# Ble_multimeter.net
KiCad netlist of a schematic drawn in EAGLE
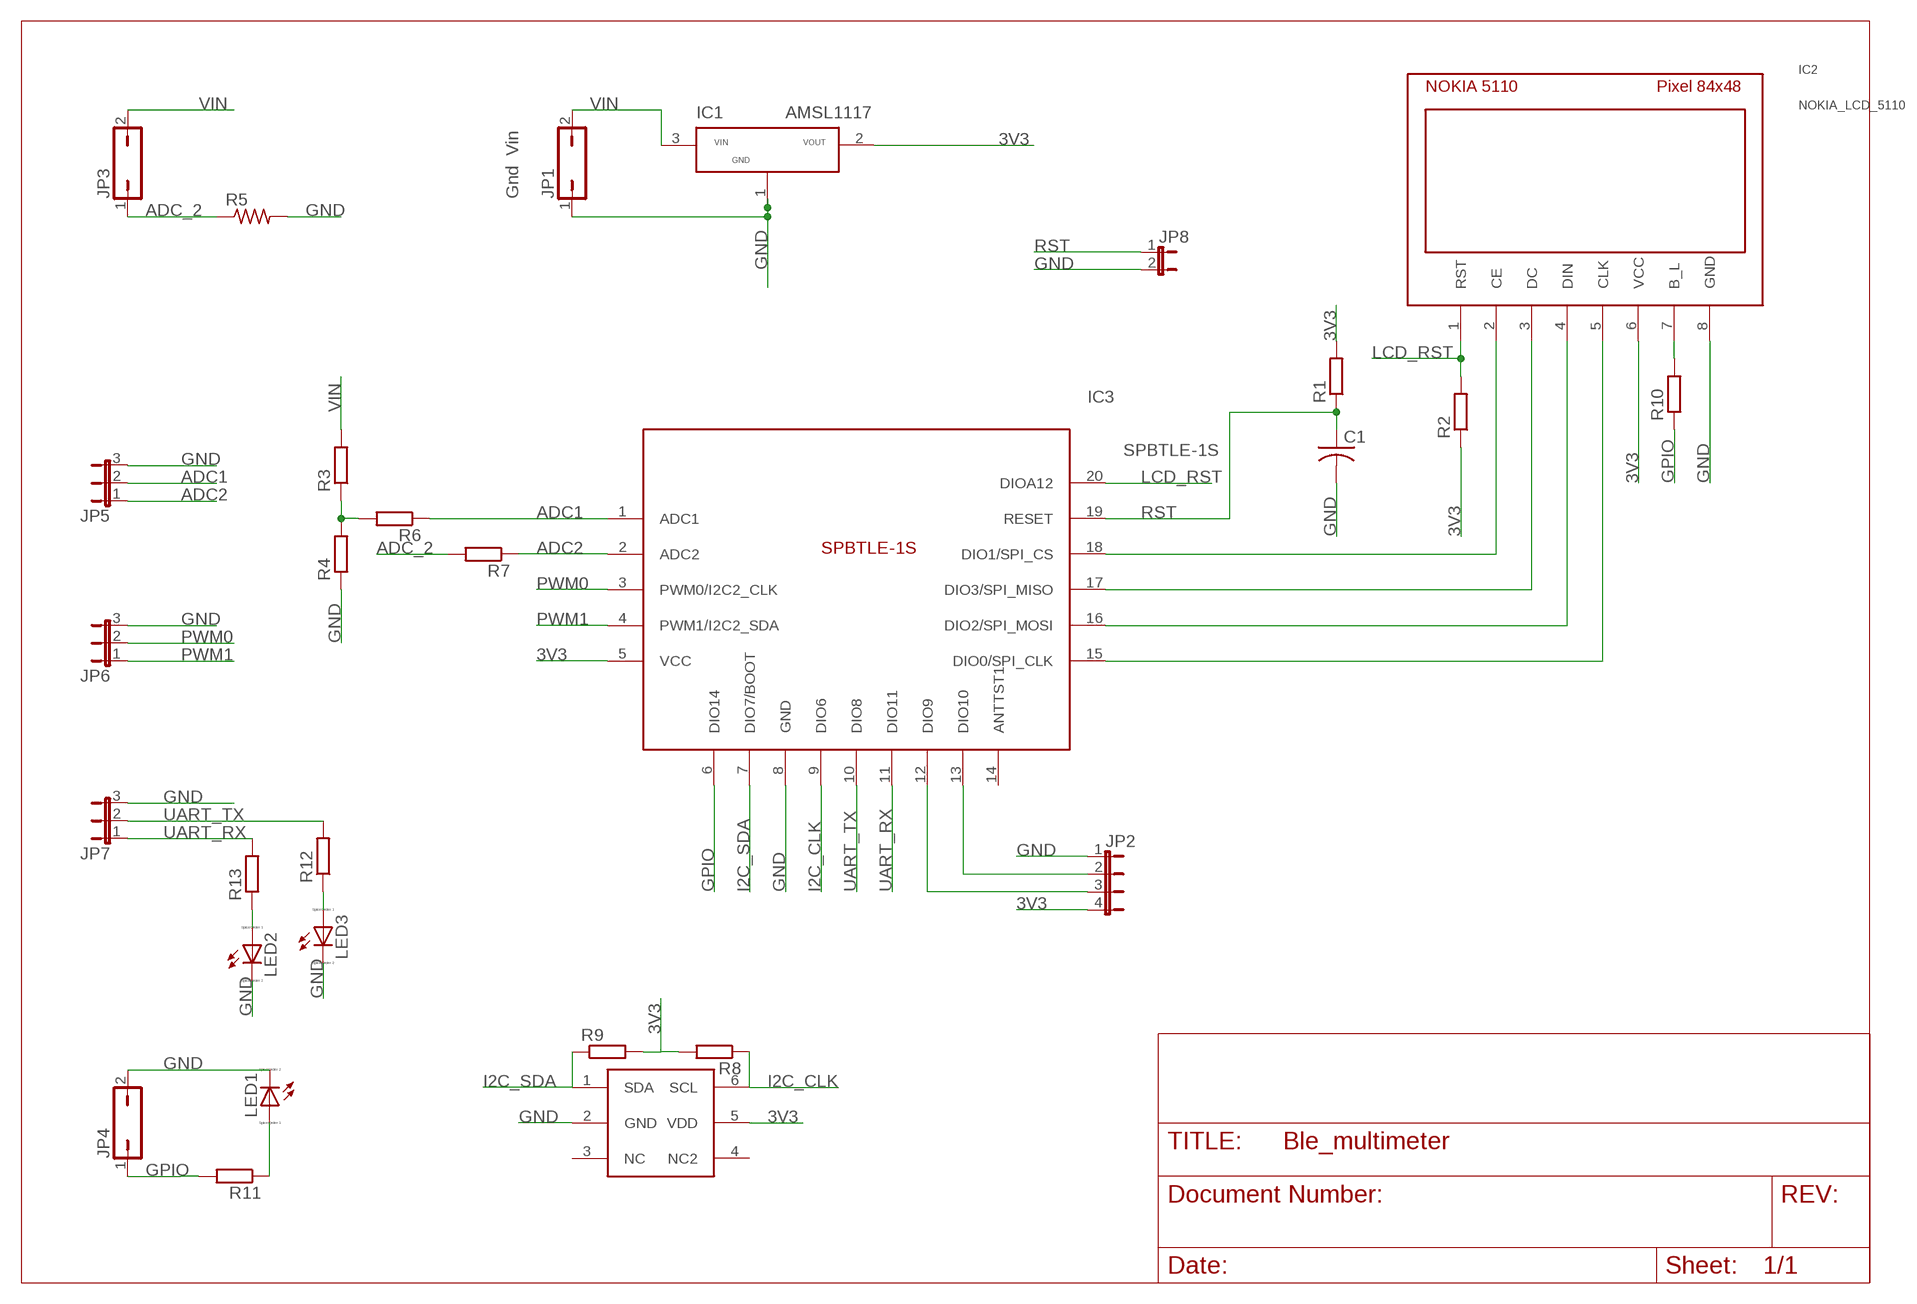
[diagram p0: schematic, sheet 1]

(export (version "E")
  (design (tool "Eeschema 10.0.6"))
  (components
    (comp (ref "C1")
      (value "C-USC0805")
      (footprint "eagle-import:C0805")
      (libsource (lib "eagle-import") (part "C-USC0805"))
    )
    (comp (ref "IC1")
      (value "AMSL1117")
      (footprint "eagle-import:SOT223")
      (libsource (lib "eagle-import") (part "AMSL1117"))
    )
    (comp (ref "IC2")
      (value "NOKIA_LCD_5110")
      (footprint "eagle-import:NOKIA_LCD_5110_8PIN")
      (libsource (lib "eagle-import") (part "NOKIA_LCD_5110"))
    )
    (comp (ref "IC3")
      (value "SPBTLE-1S")
      (footprint "eagle-import:SPBTLE-1S_SMD20")
      (libsource (lib "eagle-import") (part "SPBTLE-1S"))
    )
    (comp (ref "IC4")
      (value "HDC1080")
      (footprint "eagle-import:6_PIN_PWSON")
      (libsource (lib "eagle-import") (part "HDC1080"))
    )
    (comp (ref "JP1")
      (value "JP1Q")
      (footprint "eagle-import:JP1")
      (libsource (lib "eagle-import") (part "JP1Q"))
    )
    (comp (ref "JP2")
      (value "JP4E")
      (footprint "eagle-import:JP4")
      (libsource (lib "eagle-import") (part "JP4E"))
    )
    (comp (ref "JP3")
      (value "JP1Q")
      (footprint "eagle-import:JP1")
      (libsource (lib "eagle-import") (part "JP1Q"))
    )
    (comp (ref "JP4")
      (value "JP1Q")
      (footprint "eagle-import:JP1")
      (libsource (lib "eagle-import") (part "JP1Q"))
    )
    (comp (ref "JP5")
      (value "JP2E")
      (footprint "eagle-import:JP2")
      (libsource (lib "eagle-import") (part "JP2E"))
    )
    (comp (ref "JP6")
      (value "JP2E")
      (footprint "eagle-import:JP2")
      (libsource (lib "eagle-import") (part "JP2E"))
    )
    (comp (ref "JP7")
      (value "JP2E")
      (footprint "eagle-import:JP2")
      (libsource (lib "eagle-import") (part "JP2E"))
    )
    (comp (ref "JP8")
      (value "JP1E")
      (footprint "eagle-import:JP1")
      (libsource (lib "eagle-import") (part "JP1E"))
    )
    (comp (ref "LED1")
      (value "LED_E")
      (footprint "eagle-import:LED_1206")
      (libsource (lib "eagle-import") (part "LED_E"))
    )
    (comp (ref "LED2")
      (value "LED_E")
      (footprint "eagle-import:LED_1206")
      (libsource (lib "eagle-import") (part "LED_E"))
    )
    (comp (ref "LED3")
      (value "LED_E")
      (footprint "eagle-import:LED_1206")
      (libsource (lib "eagle-import") (part "LED_E"))
    )
    (comp (ref "R1")
      (value "R-EU_M1206")
      (footprint "eagle-import:M1206")
      (libsource (lib "eagle-import") (part "R-EU_M1206"))
    )
    (comp (ref "R2")
      (value "R-EU_M1206")
      (footprint "eagle-import:M1206")
      (libsource (lib "eagle-import") (part "R-EU_M1206"))
    )
    (comp (ref "R3")
      (value "R-EU_M1206")
      (footprint "eagle-import:M1206")
      (libsource (lib "eagle-import") (part "R-EU_M1206"))
    )
    (comp (ref "R4")
      (value "R-EU_M1206")
      (footprint "eagle-import:M1206")
      (libsource (lib "eagle-import") (part "R-EU_M1206"))
    )
    (comp (ref "R5")
      (value "R-US_0414/5V")
      (footprint "eagle-import:0414V")
      (libsource (lib "eagle-import") (part "R-US_0414/5V"))
    )
    (comp (ref "R6")
      (value "R-EU_M1206")
      (footprint "eagle-import:M1206")
      (libsource (lib "eagle-import") (part "R-EU_M1206"))
    )
    (comp (ref "R7")
      (value "R-EU_M1206")
      (footprint "eagle-import:M1206")
      (libsource (lib "eagle-import") (part "R-EU_M1206"))
    )
    (comp (ref "R8")
      (value "R-EU_M1206")
      (footprint "eagle-import:M1206")
      (libsource (lib "eagle-import") (part "R-EU_M1206"))
    )
    (comp (ref "R9")
      (value "R-EU_M1206")
      (footprint "eagle-import:M1206")
      (libsource (lib "eagle-import") (part "R-EU_M1206"))
    )
    (comp (ref "R10")
      (value "R-EU_M1206")
      (footprint "eagle-import:M1206")
      (libsource (lib "eagle-import") (part "R-EU_M1206"))
    )
    (comp (ref "R11")
      (value "R-EU_M1206")
      (footprint "eagle-import:M1206")
      (libsource (lib "eagle-import") (part "R-EU_M1206"))
    )
    (comp (ref "R12")
      (value "R-EU_M1206")
      (footprint "eagle-import:M1206")
      (libsource (lib "eagle-import") (part "R-EU_M1206"))
    )
    (comp (ref "R13")
      (value "R-EU_M1206")
      (footprint "eagle-import:M1206")
      (libsource (lib "eagle-import") (part "R-EU_M1206"))
    )
  )
  (nets
    (net (code "1") (name "/3V3") (class "Default")
      (node (ref "IC1") (pin "2") (pinfunction "P$2_2") (pintype "bidirectional"))
      (node (ref "IC2") (pin "6") (pinfunction "VCC_6") (pintype "bidirectional"))
      (node (ref "IC3") (pin "5") (pinfunction "VCC_5") (pintype "bidirectional"))
      (node (ref "IC4") (pin "5") (pinfunction "VDD_5") (pintype "bidirectional"))
      (node (ref "JP2") (pin "4") (pinfunction "4_4") (pintype "passive"))
      (node (ref "R1") (pin "2") (pinfunction "2_2") (pintype "passive"))
      (node (ref "R2") (pin "1") (pinfunction "1_1") (pintype "passive"))
      (node (ref "R8") (pin "2") (pinfunction "2_2") (pintype "passive"))
      (node (ref "R9") (pin "2") (pinfunction "2_2") (pintype "passive"))
    )
    (net (code "2") (name "/ADC1") (class "Default")
      (node (ref "IC3") (pin "1") (pinfunction "ADC1_1") (pintype "bidirectional"))
      (node (ref "JP5") (pin "2") (pinfunction "2_2") (pintype "passive"))
      (node (ref "R6") (pin "1") (pinfunction "1_1") (pintype "passive"))
    )
    (net (code "3") (name "/ADC2") (class "Default")
      (node (ref "IC3") (pin "2") (pinfunction "ADC2_2") (pintype "bidirectional"))
      (node (ref "JP5") (pin "1") (pinfunction "1_1") (pintype "passive"))
      (node (ref "R7") (pin "1") (pinfunction "1_1") (pintype "passive"))
    )
    (net (code "4") (name "/ADC_2") (class "Default")
      (node (ref "JP3") (pin "1") (pinfunction "1_1") (pintype "passive"))
      (node (ref "R5") (pin "1") (pinfunction "1_1") (pintype "passive"))
      (node (ref "R7") (pin "2") (pinfunction "2_2") (pintype "passive"))
    )
    (net (code "5") (name "/GND") (class "Default")
      (node (ref "C1") (pin "2") (pinfunction "2_2") (pintype "passive"))
      (node (ref "IC1") (pin "1") (pinfunction "P$1_1") (pintype "bidirectional"))
      (node (ref "IC2") (pin "8") (pinfunction "GND_8") (pintype "bidirectional"))
      (node (ref "IC3") (pin "8") (pinfunction "GND_8") (pintype "bidirectional"))
      (node (ref "IC4") (pin "2") (pinfunction "GND_2") (pintype "bidirectional"))
      (node (ref "JP1") (pin "1") (pinfunction "1_1") (pintype "passive"))
      (node (ref "JP2") (pin "1") (pinfunction "1_1") (pintype "passive"))
      (node (ref "JP4") (pin "2") (pinfunction "2_2") (pintype "passive"))
      (node (ref "JP5") (pin "3") (pinfunction "3_3") (pintype "passive"))
      (node (ref "JP6") (pin "3") (pinfunction "3_3") (pintype "passive"))
      (node (ref "JP7") (pin "3") (pinfunction "3_3") (pintype "passive"))
      (node (ref "JP8") (pin "2") (pinfunction "2_2") (pintype "passive"))
      (node (ref "LED1") (pin "C") (pinfunction "C_C") (pintype "passive"))
      (node (ref "LED2") (pin "C") (pinfunction "C_C") (pintype "passive"))
      (node (ref "LED3") (pin "C") (pinfunction "C_C") (pintype "passive"))
      (node (ref "R4") (pin "1") (pinfunction "1_1") (pintype "passive"))
      (node (ref "R5") (pin "2") (pinfunction "2_2") (pintype "passive"))
    )
    (net (code "6") (name "/GPIO") (class "Default")
      (node (ref "IC3") (pin "6") (pinfunction "DIO14_6") (pintype "bidirectional"))
      (node (ref "JP4") (pin "1") (pinfunction "1_1") (pintype "passive"))
      (node (ref "R10") (pin "1") (pinfunction "1_1") (pintype "passive"))
      (node (ref "R11") (pin "2") (pinfunction "2_2") (pintype "passive"))
    )
    (net (code "7") (name "/I2C_CLK") (class "Default")
      (node (ref "IC3") (pin "9") (pinfunction "DIO6_9") (pintype "bidirectional"))
      (node (ref "IC4") (pin "6") (pinfunction "SCL_6") (pintype "bidirectional"))
      (node (ref "R8") (pin "1") (pinfunction "1_1") (pintype "passive"))
    )
    (net (code "8") (name "/I2C_SDA") (class "Default")
      (node (ref "IC3") (pin "7") (pinfunction "DIO7/BOOT_7") (pintype "bidirectional"))
      (node (ref "IC4") (pin "1") (pinfunction "SDA_1") (pintype "bidirectional"))
      (node (ref "R9") (pin "1") (pinfunction "1_1") (pintype "passive"))
    )
    (net (code "9") (name "/LCD_RST") (class "Default")
      (node (ref "IC2") (pin "1") (pinfunction "RST_1") (pintype "bidirectional"))
      (node (ref "IC3") (pin "20") (pinfunction "DIOA12_20") (pintype "bidirectional"))
      (node (ref "R2") (pin "2") (pinfunction "2_2") (pintype "passive"))
    )
    (net (code "10") (name "/PWM0") (class "Default")
      (node (ref "IC3") (pin "3") (pinfunction "PWM0/I2C2_CLK_3") (pintype "bidirectional"))
      (node (ref "JP6") (pin "2") (pinfunction "2_2") (pintype "passive"))
    )
    (net (code "11") (name "/PWM1") (class "Default")
      (node (ref "IC3") (pin "4") (pinfunction "PWM1/I2C2_SDA_4") (pintype "bidirectional"))
      (node (ref "JP6") (pin "1") (pinfunction "1_1") (pintype "passive"))
    )
    (net (code "12") (name "/RST") (class "Default")
      (node (ref "C1") (pin "1") (pinfunction "1_1") (pintype "passive"))
      (node (ref "IC3") (pin "19") (pinfunction "RESET_19") (pintype "bidirectional"))
      (node (ref "JP8") (pin "1") (pinfunction "1_1") (pintype "passive"))
      (node (ref "R1") (pin "1") (pinfunction "1_1") (pintype "passive"))
    )
    (net (code "13") (name "/UART_RX") (class "Default")
      (node (ref "IC3") (pin "11") (pinfunction "DIO11_11") (pintype "bidirectional"))
      (node (ref "JP7") (pin "1") (pinfunction "1_1") (pintype "passive"))
      (node (ref "R13") (pin "2") (pinfunction "2_2") (pintype "passive"))
    )
    (net (code "14") (name "/UART_TX") (class "Default")
      (node (ref "IC3") (pin "10") (pinfunction "DIO8_10") (pintype "bidirectional"))
      (node (ref "JP7") (pin "2") (pinfunction "2_2") (pintype "passive"))
      (node (ref "R12") (pin "2") (pinfunction "2_2") (pintype "passive"))
    )
    (net (code "15") (name "/VIN") (class "Default")
      (node (ref "IC1") (pin "3") (pinfunction "P$3_3") (pintype "bidirectional"))
      (node (ref "JP1") (pin "2") (pinfunction "2_2") (pintype "passive"))
      (node (ref "JP3") (pin "2") (pinfunction "2_2") (pintype "passive"))
      (node (ref "R3") (pin "2") (pinfunction "2_2") (pintype "passive"))
    )
    (net (code "16") (name "Net-(IC2-B_L)") (class "Default")
      (node (ref "IC2") (pin "7") (pinfunction "B_L_7") (pintype "bidirectional"))
      (node (ref "R10") (pin "2") (pinfunction "2_2") (pintype "passive"))
    )
    (net (code "17") (name "Net-(IC2-CE)") (class "Default")
      (node (ref "IC2") (pin "2") (pinfunction "CE_2") (pintype "bidirectional"))
      (node (ref "IC3") (pin "18") (pinfunction "DIO1/SPI_CS_18") (pintype "bidirectional"))
    )
    (net (code "18") (name "Net-(IC2-CLK)") (class "Default")
      (node (ref "IC2") (pin "5") (pinfunction "CLK_5") (pintype "bidirectional"))
      (node (ref "IC3") (pin "15") (pinfunction "DIO0/SPI_CLK_15") (pintype "bidirectional"))
    )
    (net (code "19") (name "Net-(IC2-DC)") (class "Default")
      (node (ref "IC2") (pin "3") (pinfunction "DC_3") (pintype "bidirectional"))
      (node (ref "IC3") (pin "17") (pinfunction "DIO3/SPI_MISO_17") (pintype "bidirectional"))
    )
    (net (code "20") (name "Net-(IC2-DIN)") (class "Default")
      (node (ref "IC2") (pin "4") (pinfunction "DIN_4") (pintype "bidirectional"))
      (node (ref "IC3") (pin "16") (pinfunction "DIO2/SPI_MOSI_16") (pintype "bidirectional"))
    )
    (net (code "21") (name "Net-(IC3-DIO9)") (class "Default")
      (node (ref "IC3") (pin "12") (pinfunction "DIO9_12") (pintype "bidirectional"))
      (node (ref "JP2") (pin "3") (pinfunction "3_3") (pintype "passive"))
    )
    (net (code "22") (name "Net-(IC3-DIO10)") (class "Default")
      (node (ref "IC3") (pin "13") (pinfunction "DIO10_13") (pintype "bidirectional"))
      (node (ref "JP2") (pin "2") (pinfunction "2_2") (pintype "passive"))
    )
    (net (code "23") (name "Net-(LED1-PadA)") (class "Default")
      (node (ref "LED1") (pin "A") (pinfunction "A_A") (pintype "passive"))
      (node (ref "R11") (pin "1") (pinfunction "1_1") (pintype "passive"))
    )
    (net (code "24") (name "Net-(LED2-PadA)") (class "Default")
      (node (ref "LED2") (pin "A") (pinfunction "A_A") (pintype "passive"))
      (node (ref "R13") (pin "1") (pinfunction "1_1") (pintype "passive"))
    )
    (net (code "25") (name "Net-(LED3-PadA)") (class "Default")
      (node (ref "LED3") (pin "A") (pinfunction "A_A") (pintype "passive"))
      (node (ref "R12") (pin "1") (pinfunction "1_1") (pintype "passive"))
    )
    (net (code "26") (name "Net-(R3-Pad1)") (class "Default")
      (node (ref "R3") (pin "1") (pinfunction "1_1") (pintype "passive"))
      (node (ref "R4") (pin "2") (pinfunction "2_2") (pintype "passive"))
      (node (ref "R6") (pin "2") (pinfunction "2_2") (pintype "passive"))
    )
    (net (code "27") (name "unconnected-(IC3-ANTTST1-Pad14)") (class "Default")
      (node (ref "IC3") (pin "14") (pinfunction "ANTTST1_14") (pintype "bidirectional"))
    )
    (net (code "28") (name "unconnected-(IC4-NC-Pad3)") (class "Default")
      (node (ref "IC4") (pin "3") (pinfunction "NC_3") (pintype "bidirectional"))
    )
    (net (code "29") (name "unconnected-(IC4-NC2-Pad4)") (class "Default")
      (node (ref "IC4") (pin "4") (pinfunction "NC2_4") (pintype "bidirectional"))
    )
  )
)
